# PIXRACER-FMU-R12.net
KiCad netlist of a schematic drawn in Altium Designer
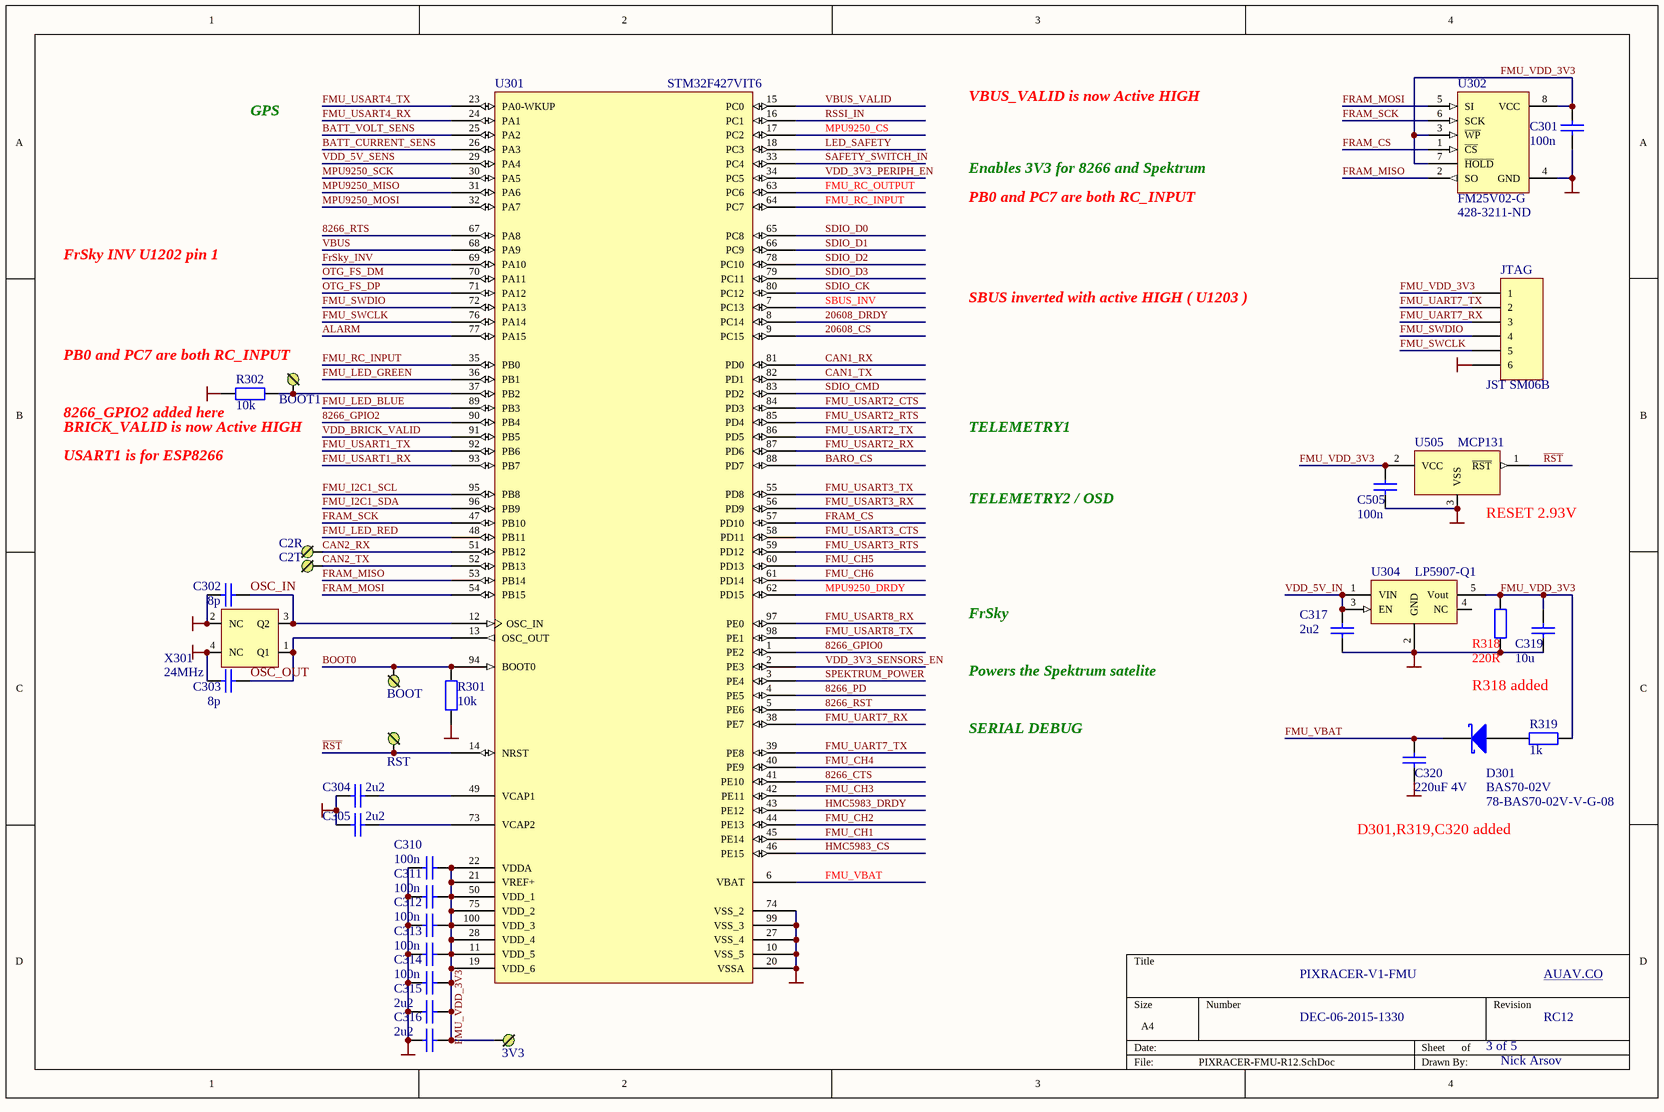
[diagram p0: PIXRACER-FMU-R12.SchDoc]

(export (version "E")
  (design (tool "Eeschema 10.0.6"))
  (components
    (comp (ref "3V3") (value "3V3") (footprint "PAD1") (libsource (lib "My_Altium") (part "PLUG")))
    (comp (ref "BOOT") (value "BOOT") (footprint "PAD1") (libsource (lib "My_Altium") (part "PLUG")))
    (comp (ref "BOOT1") (value "BOOT1") (footprint "PAD1") (libsource (lib "My_Altium") (part "PLUG")))
    (comp (ref "C2R") (value "CAN2_RX") (footprint "PAD1") (libsource (lib "My_Altium") (part "PLUG")))
    (comp (ref "C2T") (value "CAN2_TX") (footprint "PAD1") (libsource (lib "My_Altium") (part "PLUG")))
    (comp (ref "C301")
      (value "100n")
      (footprint "0402A")
      (description "Capacitor")
      (fields (field (name "PUBLISHER") "Altium Limited"))
      (libsource (lib "Miscellaneous Devices") (part "Cap"))
    )
    (comp (ref "C302")
      (value "8p")
      (footprint "0603A")
      (description "Capacitor")
      (fields (field (name "PUBLISHER") "Altium Limited"))
      (libsource (lib "Miscellaneous Devices") (part "Cap"))
    )
    (comp (ref "C303")
      (value "8p")
      (footprint "0603A")
      (description "Capacitor")
      (fields (field (name "PUBLISHER") "Altium Limited"))
      (libsource (lib "Miscellaneous Devices") (part "Cap"))
    )
    (comp (ref "C304")
      (value "2u2")
      (footprint "0402A")
      (description "Capacitor")
      (fields (field (name "PUBLISHER") "Altium Limited"))
      (libsource (lib "Miscellaneous Devices") (part "Cap"))
    )
    (comp (ref "C305")
      (value "2u2")
      (footprint "0402A")
      (description "Capacitor")
      (fields (field (name "PUBLISHER") "Altium Limited"))
      (libsource (lib "Miscellaneous Devices") (part "Cap"))
    )
    (comp (ref "C310")
      (value "100n")
      (footprint "0402A")
      (description "Capacitor")
      (fields (field (name "PUBLISHER") "Altium Limited"))
      (libsource (lib "Miscellaneous Devices") (part "Cap"))
    )
    (comp (ref "C311")
      (value "100n")
      (footprint "0402A")
      (description "Capacitor")
      (fields (field (name "PUBLISHER") "Altium Limited"))
      (libsource (lib "Miscellaneous Devices") (part "Cap"))
    )
    (comp (ref "C312")
      (value "100n")
      (footprint "0402A")
      (description "Capacitor")
      (fields (field (name "PUBLISHER") "Altium Limited"))
      (libsource (lib "Miscellaneous Devices") (part "Cap"))
    )
    (comp (ref "C313")
      (value "100n")
      (footprint "0402A")
      (description "Capacitor")
      (fields (field (name "PUBLISHER") "Altium Limited"))
      (libsource (lib "Miscellaneous Devices") (part "Cap"))
    )
    (comp (ref "C314")
      (value "100n")
      (footprint "0402A")
      (description "Capacitor")
      (fields (field (name "PUBLISHER") "Altium Limited"))
      (libsource (lib "Miscellaneous Devices") (part "Cap"))
    )
    (comp (ref "C315")
      (value "2u2")
      (footprint "0402A")
      (description "Capacitor")
      (fields (field (name "PUBLISHER") "Altium Limited"))
      (libsource (lib "Miscellaneous Devices") (part "Cap"))
    )
    (comp (ref "C316")
      (value "2u2")
      (footprint "0402A")
      (description "Capacitor")
      (fields (field (name "PUBLISHER") "Altium Limited"))
      (libsource (lib "Miscellaneous Devices") (part "Cap"))
    )
    (comp (ref "C317")
      (value "2u2")
      (footprint "0603A")
      (description "Capacitor")
      (fields (field (name "PUBLISHER") "Altium Limited"))
      (libsource (lib "Miscellaneous Devices") (part "Cap"))
    )
    (comp (ref "C319")
      (value "10u")
      (footprint "0603A")
      (description "Capacitor")
      (fields (field (name "PUBLISHER") "Altium Limited"))
      (libsource (lib "Miscellaneous Devices") (part "Cap"))
    )
    (comp (ref "C320")
      (value "220uF 4V")
      (footprint "1206A")
      (description "Capacitor")
      (fields (field (name "PUBLISHER") "Altium Limited"))
      (libsource (lib "Miscellaneous Devices") (part "Cap"))
    )
    (comp (ref "C505")
      (value "100n")
      (footprint "0402A")
      (description "Capacitor")
      (fields (field (name "PUBLISHER") "Altium Limited"))
      (libsource (lib "Miscellaneous Devices") (part "Cap"))
    )
    (comp (ref "D301")
      (value "BAS70-02V")
      (footprint "SOD-523")
      (description "Schottky Diode")
      (fields (field (name "MOUSER") "78-BAS70-02V-V-G-08") (field (name "PUBLISHER") "Altium Limited"))
      (libsource (lib "Miscellaneous Devices") (part "D Schottky"))
    )
    (comp (ref "JTAG")
      (value "JST SM06B")
      (footprint "SM06B-SRSH-TB")
      (description "Header, 6-Pin")
      (fields (field (name "PUBLISHER") "Altium Limited"))
      (libsource (lib "Miscellaneous Connectors") (part "Header 6"))
    )
    (comp (ref "R301")
      (value "10k")
      (footprint "0402A")
      (description "Resistor")
      (fields (field (name "PUBLISHER") "Altium Limited"))
      (libsource (lib "Miscellaneous Devices") (part "Res2"))
    )
    (comp (ref "R302")
      (value "10k")
      (footprint "0402A")
      (description "Resistor")
      (fields (field (name "PUBLISHER") "Altium Limited"))
      (libsource (lib "") (part "Res2_3"))
    )
    (comp (ref "R318")
      (value "220R")
      (footprint "0603A")
      (description "Resistor")
      (fields (field (name "PUBLISHER") "Altium Limited"))
      (libsource (lib "") (part "Res2_1"))
    )
    (comp (ref "R319")
      (value "1k")
      (footprint "0603A")
      (description "Resistor")
      (fields (field (name "PUBLISHER") "Altium Limited"))
      (libsource (lib "") (part "Res2_2"))
    )
    (comp (ref "RST") (value "BOOT") (footprint "PAD1") (libsource (lib "My_Altium") (part "PLUG")))
    (comp (ref "U301")
      (value "STM32F427VIT6")
      (footprint "LQFP100_L")
      (description "STM32 ARM-based 32-bit MCU with 64 Kbytes Flash, 100-pin LQFP, Industrial Temperature")
      (fields (field (name "PUBLISHER") "Altium Limited"))
      (libsource (lib "ST Microcontroller 32-Bit STM32") (part "STM32F103VBT6"))
    )
    (comp (ref "U302")
      (value "FM25V02-G")
      (footprint "SO-8_N")
      (fields (field (name "SUPPLIER PART NUMBER") "428-3211-ND"))
      (libsource (lib "My_Altium") (part "AT45DB161D-MU"))
    )
    (comp (ref "U304")
      (value "LP5907-Q1")
      (footprint "SOT23-5")
      (libsource (lib "My_Altium") (part "LP5907-Q1"))
    )
    (comp (ref "U505") (value "MCP131") (footprint "SOT-323") (libsource (lib "My_Altium") (part "MCP102")))
    (comp (ref "X301")
      (value "24MHz")
      (footprint "Crystal_2.5x2")
      (libsource (lib "My_Altium") (part "Crystal_4pin"))
    )
  )
  (nets
    (net (code "1") (name "/8266_CTS") (class "Default")
      (node (ref "U301") (pin "41") (pinfunction "PE10_41") (pintype "bidirectional"))
    )
    (net (code "2") (name "/8266_GPIO0") (class "Default")
      (node (ref "U301") (pin "1") (pinfunction "PE2_1") (pintype "bidirectional"))
    )
    (net (code "3") (name "/8266_GPIO2") (class "Default")
      (node (ref "U301") (pin "90") (pinfunction "PB4_90") (pintype "bidirectional"))
    )
    (net (code "4") (name "/8266_PD") (class "Default")
      (node (ref "U301") (pin "4") (pinfunction "PE5_4") (pintype "bidirectional"))
    )
    (net (code "5") (name "/8266_RST") (class "Default")
      (node (ref "U301") (pin "5") (pinfunction "PE6_5") (pintype "bidirectional"))
    )
    (net (code "6") (name "/8266_RTS") (class "Default")
      (node (ref "U301") (pin "67") (pinfunction "PA8_67") (pintype "bidirectional"))
    )
    (net (code "7") (name "/20608_CS") (class "Default")
      (node (ref "U301") (pin "9") (pinfunction "PC15_9") (pintype "bidirectional"))
    )
    (net (code "8") (name "/20608_DRDY") (class "Default")
      (node (ref "U301") (pin "8") (pinfunction "PC14_8") (pintype "bidirectional"))
    )
    (net (code "9") (name "/ALARM") (class "Default")
      (node (ref "U301") (pin "77") (pinfunction "PA15_77") (pintype "bidirectional"))
    )
    (net (code "10") (name "/BARO_CS") (class "Default")
      (node (ref "U301") (pin "88") (pinfunction "PD7_88") (pintype "bidirectional"))
    )
    (net (code "11") (name "/BATT_CURRENT_SENS") (class "Default")
      (node (ref "U301") (pin "26") (pinfunction "PA3_26") (pintype "bidirectional"))
    )
    (net (code "12") (name "/BATT_VOLT_SENS") (class "Default")
      (node (ref "U301") (pin "25") (pinfunction "PA2_25") (pintype "bidirectional"))
    )
    (net (code "13") (name "/BOOT0") (class "Default")
      (node (ref "BOOT") (pin "1") (pintype "passive"))
      (node (ref "R301") (pin "1") (pinfunction "1_1") (pintype "passive"))
      (node (ref "U301") (pin "94") (pinfunction "BOOT0_94") (pintype "input"))
    )
    (net (code "14") (name "/CAN1_RX") (class "Default")
      (node (ref "U301") (pin "81") (pinfunction "PD0_81") (pintype "bidirectional"))
    )
    (net (code "15") (name "/CAN1_TX") (class "Default")
      (node (ref "U301") (pin "82") (pinfunction "PD1_82") (pintype "bidirectional"))
    )
    (net (code "16") (name "/CAN2_RX") (class "Default")
      (node (ref "C2R") (pin "1") (pintype "passive"))
      (node (ref "U301") (pin "51") (pinfunction "PB12_51") (pintype "bidirectional"))
    )
    (net (code "17") (name "/CAN2_TX") (class "Default")
      (node (ref "C2T") (pin "1") (pintype "passive"))
      (node (ref "U301") (pin "52") (pinfunction "PB13_52") (pintype "bidirectional"))
    )
    (net (code "18") (name "/FMU_CH1") (class "Default")
      (node (ref "U301") (pin "45") (pinfunction "PE14_45") (pintype "bidirectional"))
    )
    (net (code "19") (name "/FMU_CH2") (class "Default")
      (node (ref "U301") (pin "44") (pinfunction "PE13_44") (pintype "bidirectional"))
    )
    (net (code "20") (name "/FMU_CH3") (class "Default")
      (node (ref "U301") (pin "42") (pinfunction "PE11_42") (pintype "bidirectional"))
    )
    (net (code "21") (name "/FMU_CH4") (class "Default")
      (node (ref "U301") (pin "40") (pinfunction "PE9_40") (pintype "bidirectional"))
    )
    (net (code "22") (name "/FMU_CH5") (class "Default")
      (node (ref "U301") (pin "60") (pinfunction "PD13_60") (pintype "bidirectional"))
    )
    (net (code "23") (name "/FMU_CH6") (class "Default")
      (node (ref "U301") (pin "61") (pinfunction "PD14_61") (pintype "bidirectional"))
    )
    (net (code "24") (name "/FMU_I2C1_SCL") (class "Default")
      (node (ref "U301") (pin "95") (pinfunction "PB8_95") (pintype "bidirectional"))
    )
    (net (code "25") (name "/FMU_I2C1_SDA") (class "Default")
      (node (ref "U301") (pin "96") (pinfunction "PB9_96") (pintype "bidirectional"))
    )
    (net (code "26") (name "/FMU_LED_BLUE") (class "Default")
      (node (ref "U301") (pin "89") (pinfunction "PB3_89") (pintype "bidirectional"))
    )
    (net (code "27") (name "/FMU_LED_GREEN") (class "Default")
      (node (ref "U301") (pin "36") (pinfunction "PB1_36") (pintype "bidirectional"))
    )
    (net (code "28") (name "/FMU_LED_RED") (class "Default")
      (node (ref "U301") (pin "48") (pinfunction "PB11_48") (pintype "bidirectional"))
    )
    (net (code "29") (name "/FMU_RC_INPUT") (class "Default")
      (node (ref "U301") (pin "35") (pinfunction "PB0_35") (pintype "bidirectional"))
      (node (ref "U301") (pin "64") (pinfunction "PC7_64") (pintype "bidirectional"))
    )
    (net (code "30") (name "/FMU_RC_OUTPUT") (class "Default")
      (node (ref "U301") (pin "63") (pinfunction "PC6_63") (pintype "bidirectional"))
    )
    (net (code "31") (name "/FMU_SWCLK") (class "Default")
      (node (ref "JTAG") (pin "5") (pinfunction "5_5") (pintype "passive"))
      (node (ref "U301") (pin "76") (pinfunction "PA14_76") (pintype "bidirectional"))
    )
    (net (code "32") (name "/FMU_SWDIO") (class "Default")
      (node (ref "JTAG") (pin "4") (pinfunction "4_4") (pintype "passive"))
      (node (ref "U301") (pin "72") (pinfunction "PA13_72") (pintype "bidirectional"))
    )
    (net (code "33") (name "/FMU_UART7_RX") (class "Default")
      (node (ref "JTAG") (pin "3") (pinfunction "3_3") (pintype "passive"))
      (node (ref "U301") (pin "38") (pinfunction "PE7_38") (pintype "bidirectional"))
    )
    (net (code "34") (name "/FMU_UART7_TX") (class "Default")
      (node (ref "JTAG") (pin "2") (pinfunction "2_2") (pintype "passive"))
      (node (ref "U301") (pin "39") (pinfunction "PE8_39") (pintype "bidirectional"))
    )
    (net (code "35") (name "/FMU_USART1_RX") (class "Default")
      (node (ref "U301") (pin "93") (pinfunction "PB7_93") (pintype "bidirectional"))
    )
    (net (code "36") (name "/FMU_USART1_TX") (class "Default")
      (node (ref "U301") (pin "92") (pinfunction "PB6_92") (pintype "bidirectional"))
    )
    (net (code "37") (name "/FMU_USART2_CTS") (class "Default")
      (node (ref "U301") (pin "84") (pinfunction "PD3_84") (pintype "bidirectional"))
    )
    (net (code "38") (name "/FMU_USART2_RTS") (class "Default")
      (node (ref "U301") (pin "85") (pinfunction "PD4_85") (pintype "bidirectional"))
    )
    (net (code "39") (name "/FMU_USART2_RX") (class "Default")
      (node (ref "U301") (pin "87") (pinfunction "PD6_87") (pintype "bidirectional"))
    )
    (net (code "40") (name "/FMU_USART2_TX") (class "Default")
      (node (ref "U301") (pin "86") (pinfunction "PD5_86") (pintype "bidirectional"))
    )
    (net (code "41") (name "/FMU_USART3_CTS") (class "Default")
      (node (ref "U301") (pin "58") (pinfunction "PD11_58") (pintype "bidirectional"))
    )
    (net (code "42") (name "/FMU_USART3_RTS") (class "Default")
      (node (ref "U301") (pin "59") (pinfunction "PD12_59") (pintype "bidirectional"))
    )
    (net (code "43") (name "/FMU_USART3_RX") (class "Default")
      (node (ref "U301") (pin "56") (pinfunction "PD9_56") (pintype "bidirectional"))
    )
    (net (code "44") (name "/FMU_USART3_TX") (class "Default")
      (node (ref "U301") (pin "55") (pinfunction "PD8_55") (pintype "bidirectional"))
    )
    (net (code "45") (name "/FMU_USART4_RX") (class "Default")
      (node (ref "U301") (pin "24") (pinfunction "PA1_24") (pintype "bidirectional"))
    )
    (net (code "46") (name "/FMU_USART4_TX") (class "Default")
      (node (ref "U301") (pin "23") (pinfunction "PA0-WKUP_23") (pintype "bidirectional"))
    )
    (net (code "47") (name "/FMU_USART8_RX") (class "Default")
      (node (ref "U301") (pin "97") (pinfunction "PE0_97") (pintype "bidirectional"))
    )
    (net (code "48") (name "/FMU_USART8_TX") (class "Default")
      (node (ref "U301") (pin "98") (pinfunction "PE1_98") (pintype "bidirectional"))
    )
    (net (code "49") (name "/FMU_VBAT") (class "Default")
      (node (ref "C320") (pin "2") (pinfunction "2_2") (pintype "passive"))
      (node (ref "D301") (pin "2") (pinfunction "K_2") (pintype "passive"))
      (node (ref "U301") (pin "6") (pinfunction "VBAT_6") (pintype "power_in"))
    )
    (net (code "50") (name "/FMU_VDD_3V3") (class "Default")
      (node (ref "3V3") (pin "1") (pintype "passive"))
      (node (ref "C301") (pin "2") (pinfunction "2_2") (pintype "passive"))
      (node (ref "C310") (pin "2") (pinfunction "2_2") (pintype "passive"))
      (node (ref "C311") (pin "2") (pinfunction "2_2") (pintype "passive"))
      (node (ref "C312") (pin "2") (pinfunction "2_2") (pintype "passive"))
      (node (ref "C313") (pin "2") (pinfunction "2_2") (pintype "passive"))
      (node (ref "C314") (pin "2") (pinfunction "2_2") (pintype "passive"))
      (node (ref "C315") (pin "2") (pinfunction "2_2") (pintype "passive"))
      (node (ref "C316") (pin "2") (pinfunction "2_2") (pintype "passive"))
      (node (ref "C319") (pin "2") (pinfunction "2_2") (pintype "passive"))
      (node (ref "C505") (pin "2") (pinfunction "2_2") (pintype "passive"))
      (node (ref "JTAG") (pin "1") (pinfunction "1_1") (pintype "passive"))
      (node (ref "R318") (pin "2") (pinfunction "2_2") (pintype "passive"))
      (node (ref "R319") (pin "1") (pinfunction "1_1") (pintype "passive"))
      (node (ref "U301") (pin "100") (pinfunction "VDD_3_100") (pintype "power_in"))
      (node (ref "U301") (pin "11") (pinfunction "VDD_5_11") (pintype "power_in"))
      (node (ref "U301") (pin "19") (pinfunction "VDD_6_19") (pintype "power_in"))
      (node (ref "U301") (pin "21") (pinfunction "VREF+_21") (pintype "power_in"))
      (node (ref "U301") (pin "22") (pinfunction "VDDA_22") (pintype "power_in"))
      (node (ref "U301") (pin "28") (pinfunction "VDD_4_28") (pintype "power_in"))
      (node (ref "U301") (pin "50") (pinfunction "VDD_1_50") (pintype "power_in"))
      (node (ref "U301") (pin "75") (pinfunction "VDD_2_75") (pintype "power_in"))
      (node (ref "U302") (pin "3") (pinfunction "~{WP}_3") (pintype "input"))
      (node (ref "U302") (pin "7") (pinfunction "~{HOLD}_7") (pintype "passive"))
      (node (ref "U302") (pin "8") (pinfunction "VCC_8") (pintype "power_in"))
      (node (ref "U304") (pin "5") (pinfunction "Vout_5") (pintype "power_in"))
      (node (ref "U505") (pin "2") (pinfunction "VCC_2") (pintype "power_in"))
    )
    (net (code "51") (name "/FRAM_CS") (class "Default")
      (node (ref "U301") (pin "57") (pinfunction "PD10_57") (pintype "bidirectional"))
      (node (ref "U302") (pin "1") (pinfunction "~{CS}_1") (pintype "input"))
    )
    (net (code "52") (name "/FRAM_MISO") (class "Default")
      (node (ref "U301") (pin "53") (pinfunction "PB14_53") (pintype "bidirectional"))
      (node (ref "U302") (pin "2") (pinfunction "SO_2") (pintype "output"))
    )
    (net (code "53") (name "/FRAM_MOSI") (class "Default")
      (node (ref "U301") (pin "54") (pinfunction "PB15_54") (pintype "bidirectional"))
      (node (ref "U302") (pin "5") (pinfunction "SI_5") (pintype "input"))
    )
    (net (code "54") (name "/FRAM_SCK") (class "Default")
      (node (ref "U301") (pin "47") (pinfunction "PB10_47") (pintype "bidirectional"))
      (node (ref "U302") (pin "6") (pinfunction "SCK_6") (pintype "input"))
    )
    (net (code "55") (name "/FrSky_INV") (class "Default")
      (node (ref "U301") (pin "69") (pinfunction "PA10_69") (pintype "bidirectional"))
    )
    (net (code "56") (name "/HMC5983_CS") (class "Default")
      (node (ref "U301") (pin "46") (pinfunction "PE15_46") (pintype "bidirectional"))
    )
    (net (code "57") (name "/HMC5983_DRDY") (class "Default")
      (node (ref "U301") (pin "43") (pinfunction "PE12_43") (pintype "bidirectional"))
    )
    (net (code "58") (name "/LED_SAFETY") (class "Default")
      (node (ref "U301") (pin "18") (pinfunction "PC3_18") (pintype "bidirectional"))
    )
    (net (code "59") (name "/MPU9250_CS") (class "Default")
      (node (ref "U301") (pin "17") (pinfunction "PC2_17") (pintype "bidirectional"))
    )
    (net (code "60") (name "/MPU9250_DRDY") (class "Default")
      (node (ref "U301") (pin "62") (pinfunction "PD15_62") (pintype "bidirectional"))
    )
    (net (code "61") (name "/MPU9250_MISO") (class "Default")
      (node (ref "U301") (pin "31") (pinfunction "PA6_31") (pintype "bidirectional"))
    )
    (net (code "62") (name "/MPU9250_MOSI") (class "Default")
      (node (ref "U301") (pin "32") (pinfunction "PA7_32") (pintype "bidirectional"))
    )
    (net (code "63") (name "/MPU9250_SCK") (class "Default")
      (node (ref "U301") (pin "30") (pinfunction "PA5_30") (pintype "bidirectional"))
    )
    (net (code "64") (name "/OSC_IN") (class "Default")
      (node (ref "C302") (pin "2") (pinfunction "2_2") (pintype "passive"))
      (node (ref "U301") (pin "12") (pinfunction "OSC_IN_12") (pintype "input"))
      (node (ref "X301") (pin "3") (pinfunction "Q2_3") (pintype "passive"))
    )
    (net (code "65") (name "/OSC_OUT") (class "Default")
      (node (ref "C303") (pin "2") (pinfunction "2_2") (pintype "passive"))
      (node (ref "U301") (pin "13") (pinfunction "OSC_OUT_13") (pintype "output"))
      (node (ref "X301") (pin "1") (pinfunction "Q1_1") (pintype "passive"))
    )
    (net (code "66") (name "/OTG_FS_DM") (class "Default")
      (node (ref "U301") (pin "70") (pinfunction "PA11_70") (pintype "bidirectional"))
    )
    (net (code "67") (name "/OTG_FS_DP") (class "Default")
      (node (ref "U301") (pin "71") (pinfunction "PA12_71") (pintype "bidirectional"))
    )
    (net (code "68") (name "/RSSI_IN") (class "Default")
      (node (ref "U301") (pin "16") (pinfunction "PC1_16") (pintype "bidirectional"))
    )
    (net (code "69") (name "/SAFETY_SWITCH_IN") (class "Default")
      (node (ref "U301") (pin "33") (pinfunction "PC4_33") (pintype "bidirectional"))
    )
    (net (code "70") (name "/SBUS_INV") (class "Default")
      (node (ref "U301") (pin "7") (pinfunction "PC13_7") (pintype "bidirectional"))
    )
    (net (code "71") (name "/SDIO_CK") (class "Default")
      (node (ref "U301") (pin "80") (pinfunction "PC12_80") (pintype "bidirectional"))
    )
    (net (code "72") (name "/SDIO_CMD") (class "Default")
      (node (ref "U301") (pin "83") (pinfunction "PD2_83") (pintype "bidirectional"))
    )
    (net (code "73") (name "/SDIO_D0") (class "Default")
      (node (ref "U301") (pin "65") (pinfunction "PC8_65") (pintype "bidirectional"))
    )
    (net (code "74") (name "/SDIO_D1") (class "Default")
      (node (ref "U301") (pin "66") (pinfunction "PC9_66") (pintype "bidirectional"))
    )
    (net (code "75") (name "/SDIO_D2") (class "Default")
      (node (ref "U301") (pin "78") (pinfunction "PC10_78") (pintype "bidirectional"))
    )
    (net (code "76") (name "/SDIO_D3") (class "Default")
      (node (ref "U301") (pin "79") (pinfunction "PC11_79") (pintype "bidirectional"))
    )
    (net (code "77") (name "/SPEKTRUM_POWER") (class "Default")
      (node (ref "U301") (pin "3") (pinfunction "PE4_3") (pintype "bidirectional"))
    )
    (net (code "78") (name "/VBUS") (class "Default")
      (node (ref "U301") (pin "68") (pinfunction "PA9_68") (pintype "bidirectional"))
    )
    (net (code "79") (name "/VBUS_VALID") (class "Default")
      (node (ref "U301") (pin "15") (pinfunction "PC0_15") (pintype "bidirectional"))
    )
    (net (code "80") (name "/VDD_3V3_PERIPH_EN") (class "Default")
      (node (ref "U301") (pin "34") (pinfunction "PC5_34") (pintype "bidirectional"))
    )
    (net (code "81") (name "/VDD_3V3_SENSORS_EN") (class "Default")
      (node (ref "U301") (pin "2") (pinfunction "PE3_2") (pintype "bidirectional"))
    )
    (net (code "82") (name "/VDD_5V_IN") (class "Default")
      (node (ref "C317") (pin "2") (pinfunction "2_2") (pintype "passive"))
      (node (ref "U304") (pin "1") (pinfunction "VIN_1") (pintype "power_in"))
      (node (ref "U304") (pin "3") (pinfunction "EN_3") (pintype "input"))
    )
    (net (code "83") (name "/VDD_5V_SENS") (class "Default")
      (node (ref "U301") (pin "29") (pinfunction "PA4_29") (pintype "bidirectional"))
    )
    (net (code "84") (name "/VDD_BRICK_VALID") (class "Default")
      (node (ref "U301") (pin "91") (pinfunction "PB5_91") (pintype "bidirectional"))
    )
    (net (code "85") (name "/~{RST}") (class "Default")
      (node (ref "RST") (pin "1") (pintype "passive"))
      (node (ref "U301") (pin "14") (pinfunction "NRST_14") (pintype "bidirectional"))
      (node (ref "U505") (pin "1") (pinfunction "~{RST}_1") (pintype "output"))
    )
    (net (code "86") (name "GND") (class "Default")
      (node (ref "C301") (pin "1") (pinfunction "1_1") (pintype "passive"))
      (node (ref "C302") (pin "1") (pinfunction "1_1") (pintype "passive"))
      (node (ref "C303") (pin "1") (pinfunction "1_1") (pintype "passive"))
      (node (ref "C304") (pin "2") (pinfunction "2_2") (pintype "passive"))
      (node (ref "C305") (pin "2") (pinfunction "2_2") (pintype "passive"))
      (node (ref "C310") (pin "1") (pinfunction "1_1") (pintype "passive"))
      (node (ref "C311") (pin "1") (pinfunction "1_1") (pintype "passive"))
      (node (ref "C312") (pin "1") (pinfunction "1_1") (pintype "passive"))
      (node (ref "C313") (pin "1") (pinfunction "1_1") (pintype "passive"))
      (node (ref "C314") (pin "1") (pinfunction "1_1") (pintype "passive"))
      (node (ref "C315") (pin "1") (pinfunction "1_1") (pintype "passive"))
      (node (ref "C316") (pin "1") (pinfunction "1_1") (pintype "passive"))
      (node (ref "C317") (pin "1") (pinfunction "1_1") (pintype "passive"))
      (node (ref "C319") (pin "1") (pinfunction "1_1") (pintype "passive"))
      (node (ref "C320") (pin "1") (pinfunction "1_1") (pintype "passive"))
      (node (ref "C505") (pin "1") (pinfunction "1_1") (pintype "passive"))
      (node (ref "JTAG") (pin "6") (pinfunction "6_6") (pintype "passive"))
      (node (ref "R301") (pin "2") (pinfunction "2_2") (pintype "passive"))
      (node (ref "R302") (pin "1") (pinfunction "1_1") (pintype "passive"))
      (node (ref "R318") (pin "1") (pinfunction "1_1") (pintype "passive"))
      (node (ref "U301") (pin "10") (pinfunction "VSS_5_10") (pintype "power_in"))
      (node (ref "U301") (pin "20") (pinfunction "VSSA_20") (pintype "power_in"))
      (node (ref "U301") (pin "27") (pinfunction "VSS_4_27") (pintype "power_in"))
      (node (ref "U301") (pin "74") (pinfunction "VSS_2_74") (pintype "power_in"))
      (node (ref "U301") (pin "99") (pinfunction "VSS_3_99") (pintype "power_in"))
      (node (ref "U302") (pin "4") (pinfunction "GND_4") (pintype "power_in"))
      (node (ref "U304") (pin "2") (pinfunction "GND_2") (pintype "power_in"))
      (node (ref "U505") (pin "3") (pinfunction "VSS_3") (pintype "power_in"))
      (node (ref "X301") (pin "2") (pinfunction "NC_2") (pintype "passive"))
      (node (ref "X301") (pin "4") (pinfunction "NC_4") (pintype "passive"))
    )
    (net (code "87") (name "Net-(D301-A)") (class "Default")
      (node (ref "D301") (pin "1") (pinfunction "A_1") (pintype "passive"))
      (node (ref "R319") (pin "2") (pinfunction "2_2") (pintype "passive"))
    )
    (net (code "88") (name "Net-(U301-PB2)") (class "Default")
      (node (ref "BOOT1") (pin "1") (pintype "passive"))
      (node (ref "R302") (pin "2") (pinfunction "2_2") (pintype "passive"))
      (node (ref "U301") (pin "37") (pinfunction "PB2_37") (pintype "bidirectional"))
    )
    (net (code "89") (name "Net-(U301-VCAP1)") (class "Default")
      (node (ref "C304") (pin "1") (pinfunction "1_1") (pintype "passive"))
      (node (ref "U301") (pin "49") (pinfunction "VCAP1_49") (pintype "passive"))
    )
    (net (code "90") (name "Net-(U301-VCAP2)") (class "Default")
      (node (ref "C305") (pin "1") (pinfunction "1_1") (pintype "passive"))
      (node (ref "U301") (pin "73") (pinfunction "VCAP2_73") (pintype "passive"))
    )
    (net (code "91") (name "unconnected-(U304-NC-Pad4)") (class "Default")
      (node (ref "U304") (pin "4") (pinfunction "NC_4") (pintype "passive"))
    )
  )
)
